# MHI-AC-Ctrl_v1_0.net
KiCad netlist of a schematic drawn in EAGLE
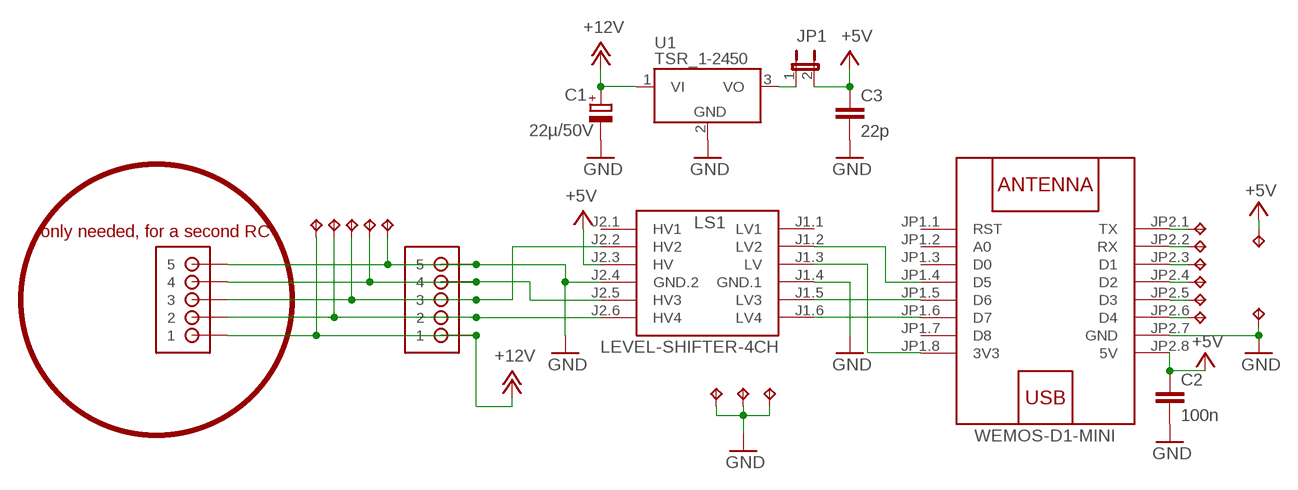
[diagram p0: schematic, sheet 1]

(export (version "E")
  (design (tool "Eeschema 10.0.6"))
  (components
    (comp (ref "C1")
      (value "22µ/50V")
      (footprint "eagle-import:E5-10,5")
      (libsource (lib "eagle-import") (part "CPOL-EUE5-10.5"))
    )
    (comp (ref "C2")
      (value "100n")
      (footprint "eagle-import:C025-024X044")
      (libsource (lib "eagle-import") (part "C-EU025-024X044"))
    )
    (comp (ref "C3")
      (value "22p")
      (footprint "eagle-import:C025-024X044")
      (libsource (lib "eagle-import") (part "C-EU025-024X044"))
    )
    (comp (ref "JP1")
      (value "JP1E")
      (footprint "eagle-import:JP1")
      (libsource (lib "eagle-import") (part "JP1E"))
    )
    (comp (ref "LS1")
      (value "LEVEL-SHIFTER-4CH")
      (footprint "eagle-import:LEVEL-SHIFTER-4CH")
      (libsource (lib "eagle-import") (part "LEVEL-SHIFTER-4CH"))
    )
    (comp (ref "TP1")
      (value "TPPAD1-13")
      (footprint "eagle-import:P1-13")
      (libsource (lib "eagle-import") (part "TPPAD1-13"))
    )
    (comp (ref "TP2")
      (value "TPPAD1-13")
      (footprint "eagle-import:P1-13")
      (libsource (lib "eagle-import") (part "TPPAD1-13"))
    )
    (comp (ref "TP3")
      (value "TPPAD1-13")
      (footprint "eagle-import:P1-13")
      (libsource (lib "eagle-import") (part "TPPAD1-13"))
    )
    (comp (ref "TP4")
      (value "TPPAD1-13")
      (footprint "eagle-import:P1-13")
      (libsource (lib "eagle-import") (part "TPPAD1-13"))
    )
    (comp (ref "TP5")
      (value "TPPAD1-13")
      (footprint "eagle-import:P1-13")
      (libsource (lib "eagle-import") (part "TPPAD1-13"))
    )
    (comp (ref "TP6")
      (value "TPPAD1-13")
      (footprint "eagle-import:P1-13")
      (libsource (lib "eagle-import") (part "TPPAD1-13"))
    )
    (comp (ref "TP7")
      (value "TPPAD1-13")
      (footprint "eagle-import:P1-13")
      (libsource (lib "eagle-import") (part "TPPAD1-13"))
    )
    (comp (ref "TP8")
      (value "TPPAD1-13")
      (footprint "eagle-import:P1-13")
      (libsource (lib "eagle-import") (part "TPPAD1-13"))
    )
    (comp (ref "TP9")
      (value "TPPAD1-13")
      (footprint "eagle-import:P1-13")
      (libsource (lib "eagle-import") (part "TPPAD1-13"))
    )
    (comp (ref "TP10")
      (value "TPPAD1-13")
      (footprint "eagle-import:P1-13")
      (libsource (lib "eagle-import") (part "TPPAD1-13"))
    )
    (comp (ref "TP11")
      (value "TPPAD1-13")
      (footprint "eagle-import:P1-13")
      (libsource (lib "eagle-import") (part "TPPAD1-13"))
    )
    (comp (ref "TP12")
      (value "TPPAD1-13")
      (footprint "eagle-import:P1-13")
      (libsource (lib "eagle-import") (part "TPPAD1-13"))
    )
    (comp (ref "TP13")
      (value "TPPAD1-13")
      (footprint "eagle-import:P1-13")
      (libsource (lib "eagle-import") (part "TPPAD1-13"))
    )
    (comp (ref "TP14")
      (value "TPPAD1-13")
      (footprint "eagle-import:P1-13")
      (libsource (lib "eagle-import") (part "TPPAD1-13"))
    )
    (comp (ref "TP15")
      (value "TPPAD1-13")
      (footprint "eagle-import:P1-13")
      (libsource (lib "eagle-import") (part "TPPAD1-13"))
    )
    (comp (ref "TP16")
      (value "TPPAD1-13")
      (footprint "eagle-import:P1-13")
      (libsource (lib "eagle-import") (part "TPPAD1-13"))
    )
    (comp (ref "U$1")
      (value "WEMOS-D1-MINI")
      (footprint "eagle-import:WEMOS-D1-MINI")
      (libsource (lib "eagle-import") (part "WEMOS-D1-MINI"))
    )
    (comp (ref "U$4")
      (value "JST-PH_5-PIN_HEADER")
      (footprint "eagle-import:JST_B5B-PH_HEADER")
      (libsource (lib "eagle-import") (part "JST-PH_5-PIN_HEADER"))
    )
    (comp (ref "U$5")
      (value "JST-PH_5-PIN_HEADER")
      (footprint "eagle-import:JST_B5B-PH_HEADER")
      (libsource (lib "eagle-import") (part "JST-PH_5-PIN_HEADER"))
    )
    (comp (ref "U1")
      (value "TSR_1-2450")
      (footprint "eagle-import:TSR-1")
      (libsource (lib "eagle-import") (part "TSR_1-24_"))
    )
  )
  (nets
    (net (code "1") (name "+5V") (class "Default")
      (node (ref "C2") (pin "1") (pinfunction "1_1") (pintype "passive"))
      (node (ref "C3") (pin "1") (pinfunction "1_1") (pintype "passive"))
      (node (ref "JP1") (pin "2") (pinfunction "2_2") (pintype "passive"))
      (node (ref "LS1") (pin "J2.3") (pinfunction "HV_J2.3") (pintype "power_in"))
      (node (ref "TP8") (pin "TP") (pinfunction "TP_TP") (pintype "input"))
      (node (ref "U$1") (pin "JP2.8") (pinfunction "5V_JP2.8") (pintype "power_in"))
    )
    (net (code "2") (name "+12V") (class "Default")
      (node (ref "C1") (pin "+") (pinfunction "+_+") (pintype "passive"))
      (node (ref "TP13") (pin "TP") (pinfunction "TP_TP") (pintype "input"))
      (node (ref "U$4") (pin "P1") (pinfunction "1_P1") (pintype "bidirectional"))
      (node (ref "U$5") (pin "P1") (pinfunction "1_P1") (pintype "bidirectional"))
      (node (ref "U1") (pin "1") (pinfunction "VI_1") (pintype "power_in"))
    )
    (net (code "3") (name "GND") (class "Default")
      (node (ref "C1") (pin "-") (pinfunction "-_-") (pintype "passive"))
      (node (ref "C2") (pin "2") (pinfunction "2_2") (pintype "passive"))
      (node (ref "C3") (pin "2") (pinfunction "2_2") (pintype "passive"))
      (node (ref "LS1") (pin "J1.4") (pinfunction "GND.1_J1.4") (pintype "power_in"))
      (node (ref "LS1") (pin "J2.4") (pinfunction "GND.2_J2.4") (pintype "power_in"))
      (node (ref "TP14") (pin "TP") (pinfunction "TP_TP") (pintype "input"))
      (node (ref "TP15") (pin "TP") (pinfunction "TP_TP") (pintype "input"))
      (node (ref "TP16") (pin "TP") (pinfunction "TP_TP") (pintype "input"))
      (node (ref "TP7") (pin "TP") (pinfunction "TP_TP") (pintype "input"))
      (node (ref "TP9") (pin "TP") (pinfunction "TP_TP") (pintype "input"))
      (node (ref "U$1") (pin "JP2.7") (pinfunction "GND_JP2.7") (pintype "power_in"))
      (node (ref "U$4") (pin "P5") (pinfunction "5_P5") (pintype "bidirectional"))
      (node (ref "U$5") (pin "P5") (pinfunction "5_P5") (pintype "bidirectional"))
      (node (ref "U1") (pin "2") (pinfunction "GND_2") (pintype "power_in"))
    )
    (net (code "4") (name "Net-(LS1-HV2)") (class "Default")
      (node (ref "LS1") (pin "J2.2") (pinfunction "HV2_J2.2") (pintype "bidirectional"))
      (node (ref "TP11") (pin "TP") (pinfunction "TP_TP") (pintype "input"))
      (node (ref "U$4") (pin "P3") (pinfunction "3_P3") (pintype "bidirectional"))
      (node (ref "U$5") (pin "P3") (pinfunction "3_P3") (pintype "bidirectional"))
    )
    (net (code "5") (name "Net-(LS1-HV3)") (class "Default")
      (node (ref "LS1") (pin "J2.5") (pinfunction "HV3_J2.5") (pintype "bidirectional"))
      (node (ref "TP10") (pin "TP") (pinfunction "TP_TP") (pintype "input"))
      (node (ref "U$4") (pin "P4") (pinfunction "4_P4") (pintype "bidirectional"))
      (node (ref "U$5") (pin "P4") (pinfunction "4_P4") (pintype "bidirectional"))
    )
    (net (code "6") (name "Net-(LS1-HV4)") (class "Default")
      (node (ref "LS1") (pin "J2.6") (pinfunction "HV4_J2.6") (pintype "bidirectional"))
      (node (ref "TP12") (pin "TP") (pinfunction "TP_TP") (pintype "input"))
      (node (ref "U$4") (pin "P2") (pinfunction "2_P2") (pintype "bidirectional"))
      (node (ref "U$5") (pin "P2") (pinfunction "2_P2") (pintype "bidirectional"))
    )
    (net (code "7") (name "Net-(LS1-LV)") (class "Default")
      (node (ref "LS1") (pin "J1.3") (pinfunction "LV_J1.3") (pintype "power_in"))
      (node (ref "U$1") (pin "JP1.8") (pinfunction "3V3_JP1.8") (pintype "power_in"))
    )
    (net (code "8") (name "Net-(LS1-LV2)") (class "Default")
      (node (ref "LS1") (pin "J1.2") (pinfunction "LV2_J1.2") (pintype "bidirectional"))
      (node (ref "U$1") (pin "JP1.4") (pinfunction "D5_JP1.4") (pintype "bidirectional"))
    )
    (net (code "9") (name "Net-(LS1-LV3)") (class "Default")
      (node (ref "LS1") (pin "J1.5") (pinfunction "LV3_J1.5") (pintype "bidirectional"))
      (node (ref "U$1") (pin "JP1.5") (pinfunction "D6_JP1.5") (pintype "bidirectional"))
    )
    (net (code "10") (name "Net-(LS1-LV4)") (class "Default")
      (node (ref "LS1") (pin "J1.6") (pinfunction "LV4_J1.6") (pintype "bidirectional"))
      (node (ref "U$1") (pin "JP1.6") (pinfunction "D7_JP1.6") (pintype "bidirectional"))
    )
    (net (code "11") (name "Net-(U$1-D1)") (class "Default")
      (node (ref "TP3") (pin "TP") (pinfunction "TP_TP") (pintype "input"))
      (node (ref "U$1") (pin "JP2.3") (pinfunction "D1_JP2.3") (pintype "bidirectional"))
    )
    (net (code "12") (name "Net-(U$1-D2)") (class "Default")
      (node (ref "TP4") (pin "TP") (pinfunction "TP_TP") (pintype "input"))
      (node (ref "U$1") (pin "JP2.4") (pinfunction "D2_JP2.4") (pintype "bidirectional"))
    )
    (net (code "13") (name "Net-(U$1-D3)") (class "Default")
      (node (ref "TP5") (pin "TP") (pinfunction "TP_TP") (pintype "input"))
      (node (ref "U$1") (pin "JP2.5") (pinfunction "D3_JP2.5") (pintype "bidirectional"))
    )
    (net (code "14") (name "Net-(U$1-D4)") (class "Default")
      (node (ref "TP6") (pin "TP") (pinfunction "TP_TP") (pintype "input"))
      (node (ref "U$1") (pin "JP2.6") (pinfunction "D4_JP2.6") (pintype "bidirectional"))
    )
    (net (code "15") (name "Net-(U$1-RX)") (class "Default")
      (node (ref "TP2") (pin "TP") (pinfunction "TP_TP") (pintype "input"))
      (node (ref "U$1") (pin "JP2.2") (pinfunction "RX_JP2.2") (pintype "bidirectional"))
    )
    (net (code "16") (name "Net-(U$1-TX)") (class "Default")
      (node (ref "TP1") (pin "TP") (pinfunction "TP_TP") (pintype "input"))
      (node (ref "U$1") (pin "JP2.1") (pinfunction "TX_JP2.1") (pintype "bidirectional"))
    )
    (net (code "17") (name "Net-(U1-VO)") (class "Default")
      (node (ref "JP1") (pin "1") (pinfunction "1_1") (pintype "passive"))
      (node (ref "U1") (pin "3") (pinfunction "VO_3") (pintype "power_in"))
    )
    (net (code "18") (name "unconnected-(LS1-HV1-PadJ2.1)") (class "Default")
      (node (ref "LS1") (pin "J2.1") (pinfunction "HV1_J2.1") (pintype "bidirectional"))
    )
    (net (code "19") (name "unconnected-(LS1-LV1-PadJ1.1)") (class "Default")
      (node (ref "LS1") (pin "J1.1") (pinfunction "LV1_J1.1") (pintype "bidirectional"))
    )
    (net (code "20") (name "unconnected-(U$1-A0-PadJP1.2)") (class "Default")
      (node (ref "U$1") (pin "JP1.2") (pinfunction "A0_JP1.2") (pintype "bidirectional"))
    )
    (net (code "21") (name "unconnected-(U$1-D0-PadJP1.3)") (class "Default")
      (node (ref "U$1") (pin "JP1.3") (pinfunction "D0_JP1.3") (pintype "bidirectional"))
    )
    (net (code "22") (name "unconnected-(U$1-D8-PadJP1.7)") (class "Default")
      (node (ref "U$1") (pin "JP1.7") (pinfunction "D8_JP1.7") (pintype "bidirectional"))
    )
    (net (code "23") (name "unconnected-(U$1-RST-PadJP1.1)") (class "Default")
      (node (ref "U$1") (pin "JP1.1") (pinfunction "RST_JP1.1") (pintype "bidirectional"))
    )
  )
)
